# Driver.net
KiCad netlist of a schematic drawn in Altium Designer
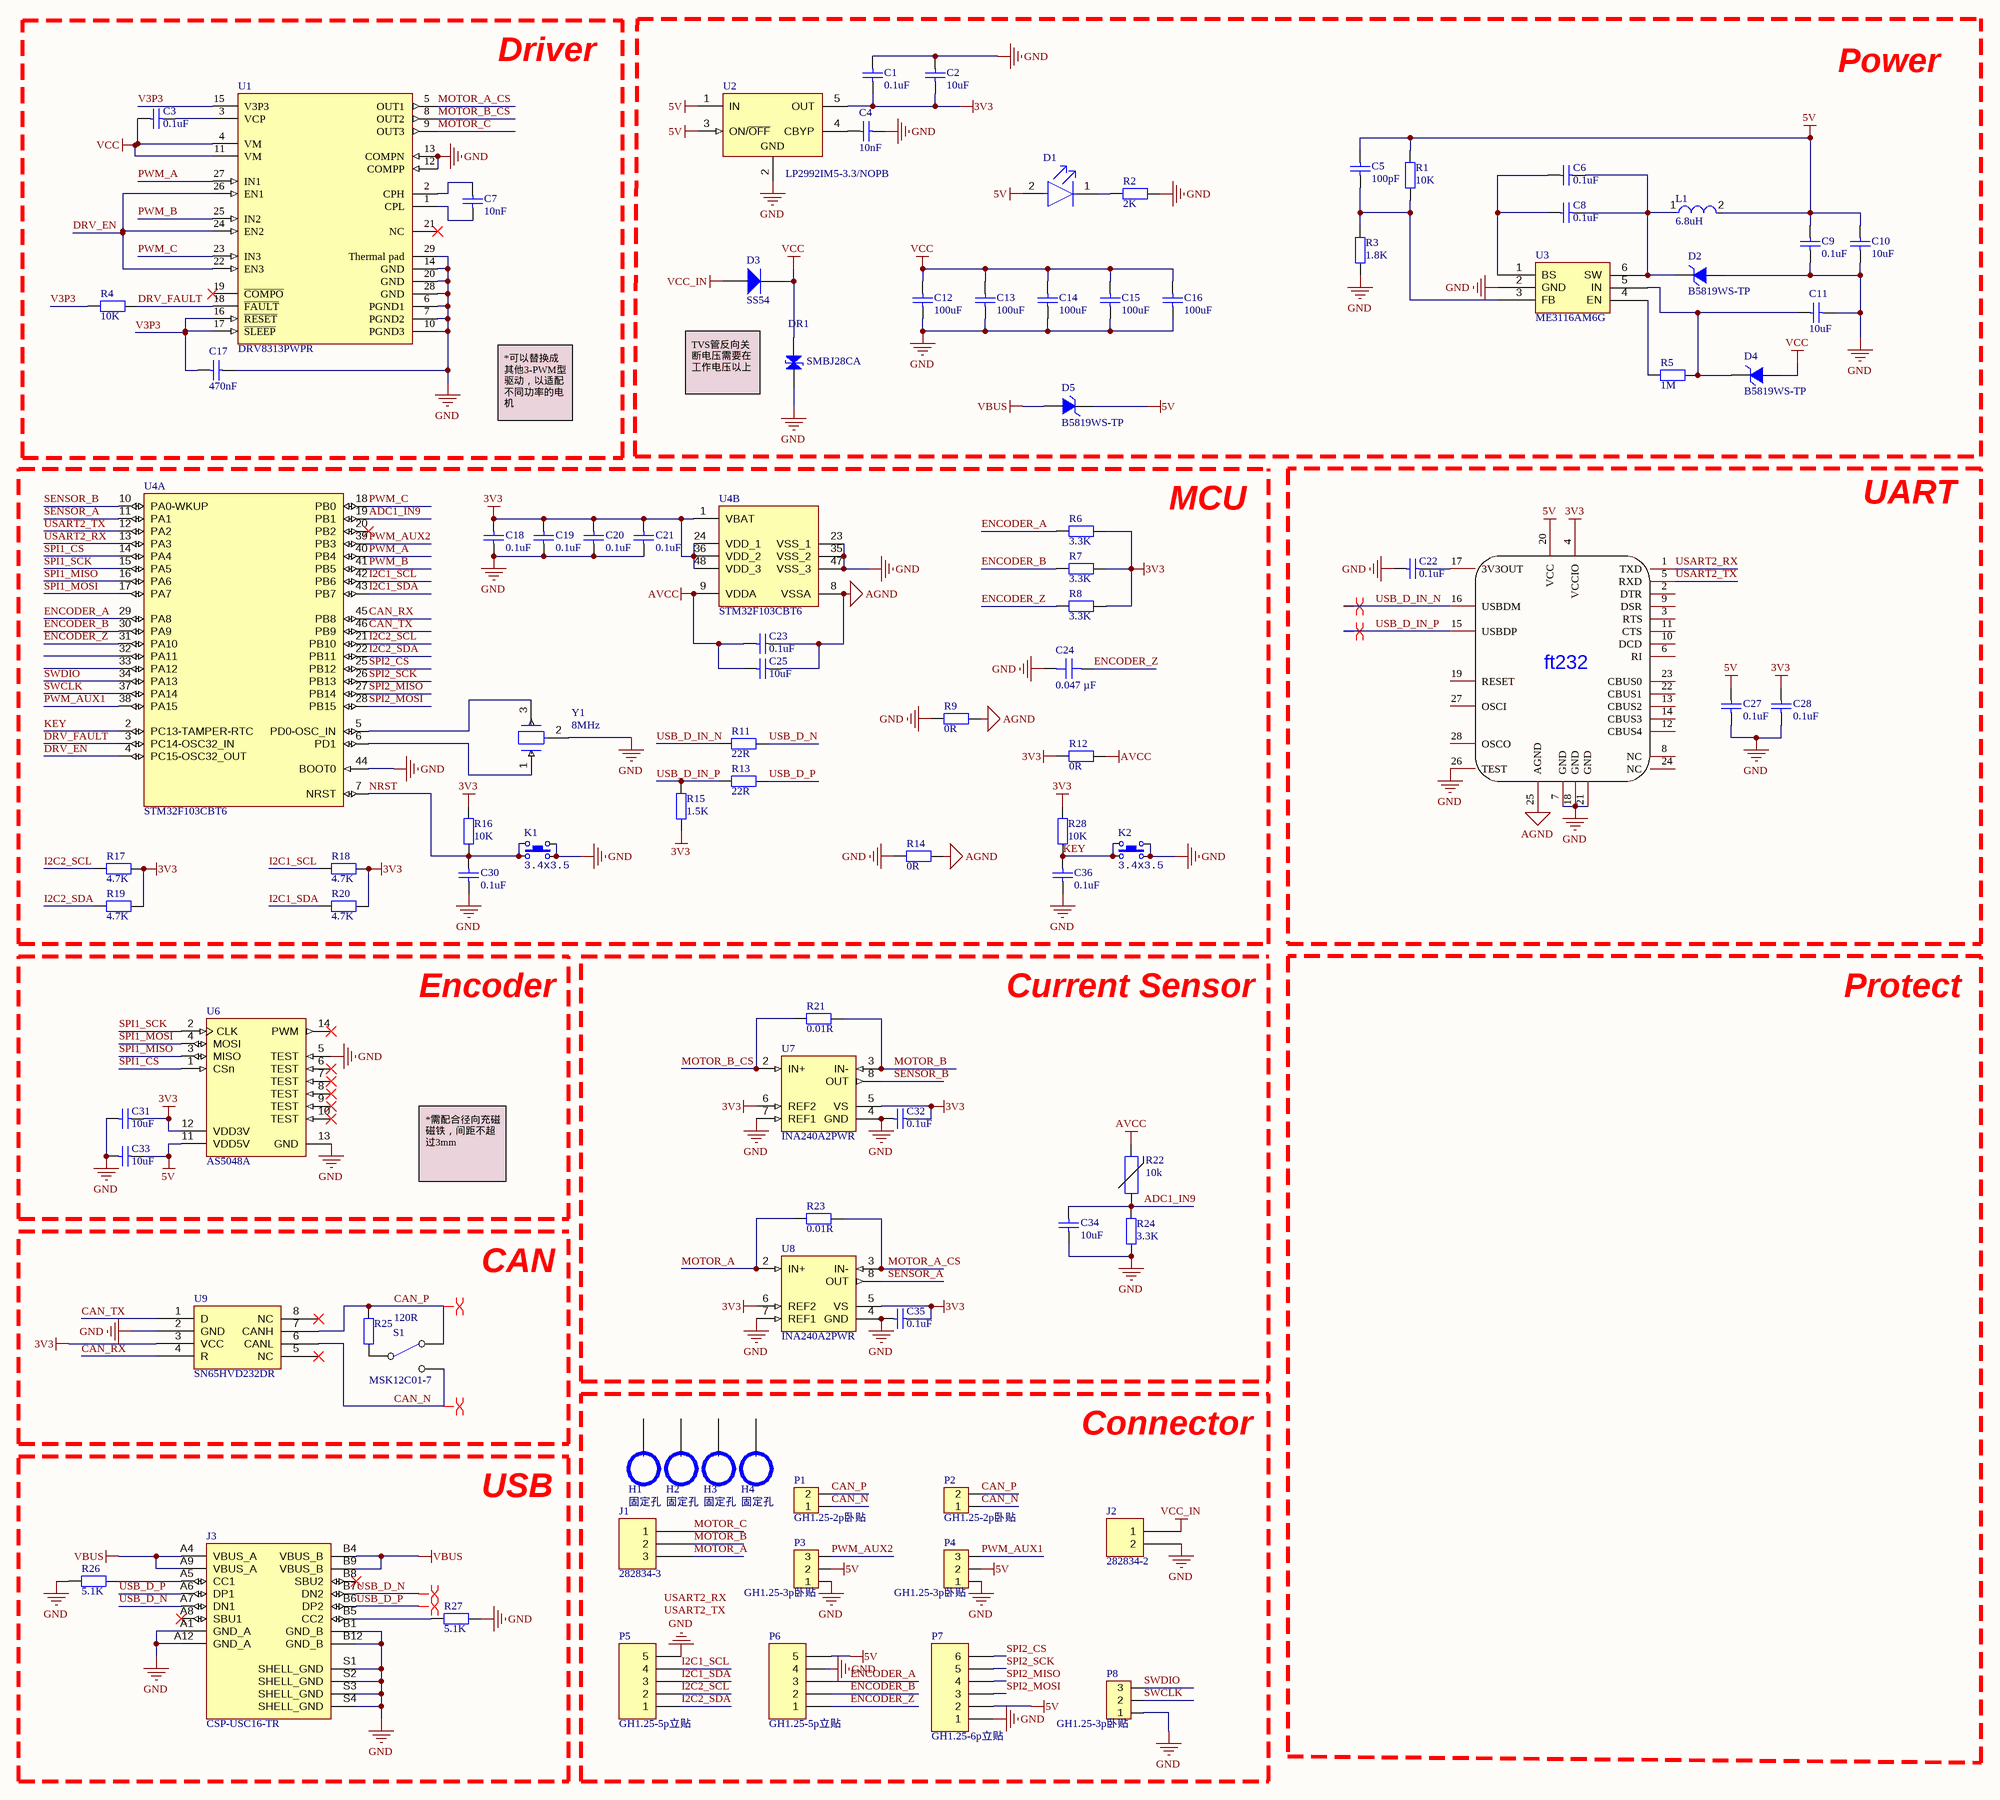
[diagram p0: Driver.SchDoc]

(export (version "E")
  (design (tool "Eeschema 10.0.6"))
  (components
    (comp (ref "C1")
      (value "0.1uF")
      (footprint "C 0402_L")
      (description "贴片电容")
      (libsource (lib "Miscellaneous Devices LC") (part "0402 100nF (104) 10% 16V"))
    )
    (comp (ref "C2")
      (value "10uF")
      (footprint "C 0402_L")
      (description "贴片电容")
      (libsource (lib "Miscellaneous Devices LC") (part "0402 100nF (104) 10% 16V"))
    )
    (comp (ref "C3")
      (value "0.1uF")
      (footprint "C 0402_L")
      (description "贴片电容")
      (libsource (lib "Miscellaneous Devices LC") (part "0402 100nF (104) 10% 16V"))
    )
    (comp (ref "C4")
      (value "10nF")
      (footprint "C 0402_L")
      (description "贴片电容")
      (libsource (lib "Miscellaneous Devices LC") (part "0402 100nF (104) 10% 16V"))
    )
    (comp (ref "C5")
      (value "100pF")
      (footprint "C 0402_L")
      (description "贴片电容")
      (libsource (lib "Miscellaneous Devices LC") (part "0402 100pF (101) 5% 50V"))
    )
    (comp (ref "C6")
      (value "0.1uF")
      (footprint "C 0402_L")
      (description "贴片电容")
      (libsource (lib "Miscellaneous Devices LC") (part "0402 100nF (104) 10% 16V"))
    )
    (comp (ref "C7")
      (value "10nF")
      (footprint "C 0402_L")
      (description "贴片电容")
      (libsource (lib "Miscellaneous Devices LC") (part "0402 10nF (103) 10% 50V"))
    )
    (comp (ref "C8")
      (value "0.1uF")
      (footprint "C 0402_L")
      (description "贴片电容")
      (libsource (lib "Miscellaneous Devices LC") (part "0402 100nF (104) 10% 16V"))
    )
    (comp (ref "C9")
      (value "0.1uF")
      (footprint "C 0402_L")
      (description "贴片电容")
      (libsource (lib "Miscellaneous Devices LC") (part "0402 100nF (104) 10% 16V"))
    )
    (comp (ref "C10")
      (value "10uF")
      (footprint "C 0402_L")
      (description "贴片电容")
      (libsource (lib "Miscellaneous Devices LC") (part "0402 100nF (104) 10% 16V"))
    )
    (comp (ref "C11")
      (value "10uF")
      (footprint "C 0402_L")
      (description "贴片电容")
      (libsource (lib "Miscellaneous Devices LC") (part "0402 100nF (104) 10% 16V"))
    )
    (comp (ref "C12")
      (value "100uF")
      (footprint "CAPC3216X190X55LL30T25")
      (description "Chip Capacitor, 100 uF, +/- 20%, 6.3 V, -55 to 85 degC, 1206 (3216 Metric), RoHS, Tape and Reel")
      (fields (field (name "TOLERANCE") "20%") (field (name "PARTNUMBER") "GRM31CR60J107ME39L"))
      (libsource (lib "Altium Content Vault") (part "CAP-NP-2"))
    )
    (comp (ref "C13")
      (value "100uF")
      (footprint "CAPC3216X190X55LL30T25")
      (description "Chip Capacitor, 100 uF, +/- 20%, 6.3 V, -55 to 85 degC, 1206 (3216 Metric), RoHS, Tape and Reel")
      (fields (field (name "TOLERANCE") "20%") (field (name "PARTNUMBER") "GRM31CR60J107ME39L"))
      (libsource (lib "Altium Content Vault") (part "CAP-NP-2"))
    )
    (comp (ref "C14")
      (value "100uF")
      (footprint "CAPC3216X190X55LL30T25")
      (description "Chip Capacitor, 100 uF, +/- 20%, 6.3 V, -55 to 85 degC, 1206 (3216 Metric), RoHS, Tape and Reel")
      (fields (field (name "TOLERANCE") "20%") (field (name "PARTNUMBER") "GRM31CR60J107ME39L"))
      (libsource (lib "Altium Content Vault") (part "CAP-NP-2"))
    )
    (comp (ref "C15")
      (value "100uF")
      (footprint "CAPC3216X190X55LL30T25")
      (description "Chip Capacitor, 100 uF, +/- 20%, 6.3 V, -55 to 85 degC, 1206 (3216 Metric), RoHS, Tape and Reel")
      (fields (field (name "TOLERANCE") "20%") (field (name "PARTNUMBER") "GRM31CR60J107ME39L"))
      (libsource (lib "Altium Content Vault") (part "CAP-NP-2"))
    )
    (comp (ref "C16")
      (value "100uF")
      (footprint "CAPC3216X190X55LL30T25")
      (description "Chip Capacitor, 100 uF, +/- 20%, 6.3 V, -55 to 85 degC, 1206 (3216 Metric), RoHS, Tape and Reel")
      (fields (field (name "TOLERANCE") "20%") (field (name "PARTNUMBER") "GRM31CR60J107ME39L"))
      (libsource (lib "Altium Content Vault") (part "CAP-NP-2"))
    )
    (comp (ref "C17")
      (value "470nF")
      (footprint "C 0402_L")
      (description "贴片电容")
      (libsource (lib "Miscellaneous Devices LC") (part "0402 470nF (474) 10% 10V"))
    )
    (comp (ref "C18")
      (value "0.1uF")
      (footprint "C 0402_L")
      (description "贴片电容")
      (libsource (lib "Miscellaneous Devices LC") (part "0402 100nF (104) 10% 16V"))
    )
    (comp (ref "C19")
      (value "0.1uF")
      (footprint "C 0402_L")
      (description "贴片电容")
      (libsource (lib "Miscellaneous Devices LC") (part "0402 100nF (104) 10% 16V"))
    )
    (comp (ref "C20")
      (value "0.1uF")
      (footprint "C 0402_L")
      (description "贴片电容")
      (libsource (lib "Miscellaneous Devices LC") (part "0402 100nF (104) 10% 16V"))
    )
    (comp (ref "C21")
      (value "0.1uF")
      (footprint "C 0402_L")
      (description "贴片电容")
      (libsource (lib "Miscellaneous Devices LC") (part "0402 100nF (104) 10% 16V"))
    )
    (comp (ref "C22")
      (value "0.1uF")
      (footprint "C 0402_L")
      (description "贴片电容")
      (libsource (lib "Miscellaneous Devices LC") (part "0402 100nF (104) 10% 16V"))
    )
    (comp (ref "C23")
      (value "0.1uF")
      (footprint "C 0402_L")
      (description "贴片电容")
      (libsource (lib "Miscellaneous Devices LC") (part "0402 100nF (104) 10% 16V"))
    )
    (comp (ref "C24")
      (value "0.047 µF")
      (footprint "CAP 0402_1005")
      (description "CAP CER 0402 47NF 25V X7R 10%")
      (fields (field (name "PART NUMBER") "C0402C473K3REC7867") (field (name "MANUFACTURER") "KEMET"))
      (libsource (lib "Celestial Altium Library - altium_library") (part "Capacitor"))
    )
    (comp (ref "C25")
      (value "10uF")
      (footprint "C 0402_L")
      (description "贴片电容")
      (libsource (lib "Miscellaneous Devices LC") (part "0402 100nF (104) 10% 16V"))
    )
    (comp (ref "C27")
      (value "0.1uF")
      (footprint "C 0402_L")
      (description "贴片电容")
      (libsource (lib "Miscellaneous Devices LC") (part "0402 100nF (104) 10% 16V"))
    )
    (comp (ref "C28")
      (value "0.1uF")
      (footprint "C 0402_L")
      (description "贴片电容")
      (libsource (lib "Miscellaneous Devices LC") (part "0402 100nF (104) 10% 16V"))
    )
    (comp (ref "C30")
      (value "0.1uF")
      (footprint "C 0402_L")
      (description "贴片电容")
      (libsource (lib "Miscellaneous Devices LC") (part "0402 100nF (104) 10% 16V"))
    )
    (comp (ref "C31")
      (value "10uF")
      (footprint "C 0402_L")
      (description "贴片电容")
      (libsource (lib "Miscellaneous Devices LC") (part "0402 100nF (104) 10% 16V"))
    )
    (comp (ref "C32")
      (value "0.1uF")
      (footprint "C 0402_L")
      (description "贴片电容")
      (libsource (lib "Miscellaneous Devices LC") (part "0402 100nF (104) 10% 16V"))
    )
    (comp (ref "C33")
      (value "10uF")
      (footprint "C 0402_L")
      (description "贴片电容")
      (libsource (lib "Miscellaneous Devices LC") (part "0402 100nF (104) 10% 16V"))
    )
    (comp (ref "C34")
      (value "10uF")
      (footprint "C 0402_L")
      (description "贴片电容")
      (libsource (lib "Miscellaneous Devices LC") (part "0402 100nF (104) 10% 16V"))
    )
    (comp (ref "C35")
      (value "0.1uF")
      (footprint "C 0402_L")
      (description "贴片电容")
      (libsource (lib "Miscellaneous Devices LC") (part "0402 100nF (104) 10% 16V"))
    )
    (comp (ref "C36")
      (value "0.1uF")
      (footprint "C 0402_L")
      (description "贴片电容")
      (libsource (lib "Miscellaneous Devices LC") (part "0402 100nF (104) 10% 16V"))
    )
    (comp (ref "D1")
      (value "~")
      (footprint "FP-APHHS1005CGCK-MFG")
      (description "LED GREEN CLEAR CHIP SMD")
      (libsource (lib "Altium Content Vault") (part "8706943c75ba83719d021d2fdc84c58"))
    )
    (comp (ref "D2")
      (value "B5819WS-TP")
      (footprint "SOD-523")
      (description "5.1V/1W稳压管")
      (fields (field (name "版权归属") "源创客"))
      (libsource (lib "*") (part "1N4733"))
    )
    (comp (ref "D3")
      (value "SS54")
      (footprint "SMA(DO-214AC)_S1")
      (description "二极管")
      (libsource (lib "Miscellaneous Devices LC") (part "SMA(DO-214AC) SS54"))
    )
    (comp (ref "D4")
      (value "B5819WS-TP")
      (footprint "SOD-523")
      (description "5.1V/1W稳压管")
      (fields (field (name "版权归属") "源创客"))
      (libsource (lib "*") (part "1N4733"))
    )
    (comp (ref "D5")
      (value "B5819WS-TP")
      (footprint "SOD-523")
      (description "5.1V/1W稳压管")
      (fields (field (name "版权归属") "源创客"))
      (libsource (lib "*") (part "1N4733"))
    )
    (comp (ref "DR1")
      (value "SMBJ28CA")
      (footprint "SMB")
      (description "瞬态电压抑制二极管")
      (fields (field (name "版权归属") "源创客"))
      (libsource (lib "*") (part "DR"))
    )
    (comp (ref "H1") (value "固定孔") (footprint "铜柱孔3") (libsource (lib "Rocos-FOC") (part "固定孔")))
    (comp (ref "H2") (value "固定孔") (footprint "铜柱孔3") (libsource (lib "Rocos-FOC") (part "固定孔")))
    (comp (ref "H3") (value "固定孔") (footprint "铜柱孔3") (libsource (lib "Rocos-FOC") (part "固定孔")))
    (comp (ref "H4") (value "固定孔") (footprint "铜柱孔3") (libsource (lib "Rocos-FOC") (part "固定孔")))
    (comp (ref "J1")
      (value "282834-3")
      (footprint "TE 282834-3")
      (description "TERM BLK 3P SIDE ENT 2.54MM PCB")
      (fields (field (name "MANUFACTURER") "TE Connectivity AMP Connectors") (field (name "VOLTAGE") "150V"))
      (libsource (lib "Rocos-FOC") (part "3 Pin"))
    )
    (comp (ref "J2")
      (value "282834-2")
      (footprint "TE 282834-2")
      (description "TERM BLK 2P SIDE ENT 2.54MM PCB")
      (fields (field (name "MANUFACTURER") "TE Connectivity AMP Connectors") (field (name "VOLTAGE") "150V"))
      (libsource (lib "Rocos-FOC") (part "2 Pin"))
    )
    (comp (ref "J3")
      (value "CSP-USC16-TR")
      (footprint "VALCON_CSP-USC16-TR")
      (description "CSP-USC16-TR Valcon USB Type C Surface Mount PCB Socket")
      (fields (field (name "MF") "Valcon"))
      (libsource (lib "Rocos-FOC") (part "CSP-USC16-TR"))
    )
    (comp (ref "K1")
      (value "3.4x3.5")
      (footprint "ButtonTACT_3.5*3.55_90")
      (description "Button")
      (fields (field (name "Comment") "TACT 4P"))
      (libsource (lib "Ctrl-FOC-Lite") (part "ButtonTACT"))
    )
    (comp (ref "K2")
      (value "3.4x3.5")
      (footprint "ButtonTACT_3.5*3.55_90")
      (description "Button")
      (fields (field (name "Comment") "TACT 4P"))
      (libsource (lib "Ctrl-FOC-Lite") (part "ButtonTACT"))
    )
    (comp (ref "L1")
      (value "6.8uH")
      (footprint "FP-LQH2MCN_52-MFG")
      (description "Wire Wound Ferrite Inductor for Power Lines 6.8μH ±20% 1.6Ω 285mA 0806")
      (fields (field (name "TOLERANCE") "20%"))
      (libsource (lib "Altium Content Vault") (part "725321dda6339637d4d059423bc1c3c"))
    )
    (comp (ref "P1")
      (value "GH1.25-2p卧贴")
      (footprint "GH1.25-2P")
      (libsource (lib "Rocos-FOC") (part "SH1.0-2P"))
    )
    (comp (ref "P2")
      (value "GH1.25-2p卧贴")
      (footprint "GH1.25-2P")
      (libsource (lib "Rocos-FOC") (part "SH1.0-2P"))
    )
    (comp (ref "P3")
      (value "GH1.25-3p卧贴")
      (footprint "GH1.25-3P")
      (description "Header")
      (libsource (lib "Rocos-FOC") (part "HDR1x3_2.54"))
    )
    (comp (ref "P4")
      (value "GH1.25-3p卧贴")
      (footprint "GH1.25-3P")
      (description "Header")
      (libsource (lib "Rocos-FOC") (part "HDR1x3_2.54"))
    )
    (comp (ref "P5")
      (value "GH1.25-5p立贴")
      (footprint "GH1.25-5p")
      (description "Header, 5-Pin")
      (fields (field (name "PUBLISHER") "Altium Limited"))
      (libsource (lib "Rocos-FOC") (part "MHDR1X5"))
    )
    (comp (ref "P6")
      (value "GH1.25-5p立贴")
      (footprint "GH1.25-5p")
      (description "Header, 5-Pin")
      (fields (field (name "PUBLISHER") "Altium Limited"))
      (libsource (lib "Rocos-FOC") (part "MHDR1X5"))
    )
    (comp (ref "P7")
      (value "GH1.25-6p立贴")
      (footprint "GH1.25-6p")
      (description "Header, 6-Pin")
      (fields (field (name "PUBLISHER") "Altium Limited"))
      (libsource (lib "Rocos-FOC") (part "MHDR1X6"))
    )
    (comp (ref "P8")
      (value "GH1.25-3p卧贴")
      (footprint "GH1.25-3P")
      (description "Header")
      (libsource (lib "Rocos-FOC") (part "HDR1x3_2.54"))
    )
    (comp (ref "R1")
      (value "10K")
      (footprint "R 0402_L")
      (description "贴片电阻")
      (libsource (lib "") (part "0402 1.2KΩ (1201) 1%_1"))
    )
    (comp (ref "R2")
      (value "2K")
      (footprint "R 0402_L")
      (description "贴片电阻")
      (libsource (lib "") (part "0402 2KΩ (2001) 1%_1"))
    )
    (comp (ref "R3")
      (value "1.8K")
      (footprint "R 0402_L")
      (description "贴片电阻")
      (libsource (lib "") (part "0402 1.2KΩ (1201) 1%_1"))
    )
    (comp (ref "R4")
      (value "10K")
      (footprint "R 0402_L")
      (description "贴片电阻")
      (libsource (lib "Miscellaneous Devices LC") (part "0402 1.2KΩ (1201) 1%"))
    )
    (comp (ref "R5")
      (value "1M")
      (footprint "R 0402_L")
      (description "贴片电阻")
      (libsource (lib "Miscellaneous Devices LC") (part "0402 2KΩ (2001) 1%"))
    )
    (comp (ref "R6")
      (value "3.3K")
      (footprint "R 0402_L")
      (description "贴片电阻")
      (libsource (lib "Miscellaneous Devices LC") (part "0402 3.3KΩ (3301) 1%"))
    )
    (comp (ref "R7")
      (value "3.3K")
      (footprint "R 0402_L")
      (description "贴片电阻")
      (libsource (lib "Miscellaneous Devices LC") (part "0402 3.3KΩ (3301) 1%"))
    )
    (comp (ref "R8")
      (value "3.3K")
      (footprint "R 0402_L")
      (description "贴片电阻")
      (libsource (lib "Miscellaneous Devices LC") (part "0402 3.3KΩ (3301) 1%"))
    )
    (comp (ref "R9")
      (value "0R")
      (footprint "R 0402_L")
      (description "贴片电阻")
      (libsource (lib "Miscellaneous Devices LC") (part "0402 0Ω (0R0) 1%"))
    )
    (comp (ref "R11")
      (value "22R")
      (footprint "R 0402_L")
      (description "贴片电阻")
      (libsource (lib "") (part "0402 22Ω (22R0) 1%_1"))
    )
    (comp (ref "R12")
      (value "0R")
      (footprint "R 0402_L")
      (description "贴片电阻")
      (libsource (lib "Miscellaneous Devices LC") (part "0402 0Ω (0R0) 1%"))
    )
    (comp (ref "R13")
      (value "22R")
      (footprint "R 0402_L")
      (description "贴片电阻")
      (libsource (lib "") (part "0402 22Ω (22R0) 1%_1"))
    )
    (comp (ref "R14")
      (value "0R")
      (footprint "R 0402_L")
      (description "贴片电阻")
      (libsource (lib "Miscellaneous Devices LC") (part "0402 0Ω (0R0) 1%"))
    )
    (comp (ref "R15")
      (value "1.5K")
      (footprint "R 0402_L")
      (description "贴片电阻")
      (libsource (lib "Miscellaneous Devices LC") (part "0402 1.5KΩ (1501) 1%"))
    )
    (comp (ref "R16")
      (value "10K")
      (footprint "R 0402_L")
      (description "贴片电阻")
      (libsource (lib "Miscellaneous Devices LC") (part "0402 10KΩ (1002) 1%"))
    )
    (comp (ref "R17")
      (value "4.7K")
      (footprint "R 0402_L")
      (description "贴片电阻")
      (libsource (lib "Miscellaneous Devices LC") (part "0402 4.7KΩ (4701) 1%"))
    )
    (comp (ref "R18")
      (value "4.7K")
      (footprint "R 0402_L")
      (description "贴片电阻")
      (libsource (lib "Miscellaneous Devices LC") (part "0402 4.7KΩ (4701) 1%"))
    )
    (comp (ref "R19")
      (value "4.7K")
      (footprint "R 0402_L")
      (description "贴片电阻")
      (libsource (lib "Miscellaneous Devices LC") (part "0402 4.7KΩ (4701) 1%"))
    )
    (comp (ref "R20")
      (value "4.7K")
      (footprint "R 0402_L")
      (description "贴片电阻")
      (libsource (lib "Miscellaneous Devices LC") (part "0402 4.7KΩ (4701) 1%"))
    )
    (comp (ref "R21")
      (value "0.01R")
      (footprint "R 0402_L")
      (description "贴片电阻")
      (libsource (lib "Miscellaneous Devices LC") (part "0402 22Ω (22R0) 1%"))
    )
    (comp (ref "R22")
      (value "10k")
      (footprint "RES_0402")
      (description "THERMISTOR 10K OHM NTC 0402 SMD")
      (fields (field (name "Comment") "NCP15XH103F03RC"))
      (libsource (lib "Ctrl-FOC-Lite") (part "NCP15XH103F03RC"))
    )
    (comp (ref "R23")
      (value "0.01R")
      (footprint "R 0402_L")
      (description "贴片电阻")
      (libsource (lib "Miscellaneous Devices LC") (part "0402 22Ω (22R0) 1%"))
    )
    (comp (ref "R24")
      (value "3.3K")
      (footprint "R 0402_L")
      (description "贴片电阻")
      (libsource (lib "") (part "0402 3.3KΩ (3301) 1%_1"))
    )
    (comp (ref "R25")
      (value "120R")
      (footprint "R 0402_L")
      (description "贴片电阻")
      (libsource (lib "Miscellaneous Devices LC") (part "0402 120Ω (1200) 1%"))
    )
    (comp (ref "R26")
      (value "5.1K")
      (footprint "R 0402_L")
      (description "贴片电阻")
      (libsource (lib "Miscellaneous Devices LC") (part "0402 1.2KΩ (1201) 1%"))
    )
    (comp (ref "R27")
      (value "5.1K")
      (footprint "R 0402_L")
      (description "贴片电阻")
      (libsource (lib "Miscellaneous Devices LC") (part "0402 1.2KΩ (1201) 1%"))
    )
    (comp (ref "R28")
      (value "10K")
      (footprint "R 0402_L")
      (description "贴片电阻")
      (libsource (lib "Miscellaneous Devices LC") (part "0402 10KΩ (1002) 1%"))
    )
    (comp (ref "S1")
      (value "MSK12C01-7")
      (footprint "MSK-12C01-07")
      (libsource (lib "闹钟") (part "T8013三脚两档钮子开关"))
    )
    (comp (ref "U1")
      (value "DRV8313PWPR")
      (footprint "FP-PWP0028C-IPC_B")
      (description "IC MOTOR DRIVER 8V-60V 28HTSSOP")
      (libsource (lib "Altium Content Vault") (part "6c5e8d1d79df7918d4eb9ae5de6b4b8"))
    )
    (comp (ref "U2")
      (value "LP2992IM5-3.3/NOPB")
      (footprint "DBV0005A_L")
      (description "Micropower 250 mA Low-Noise Ultra Low-Dropout Regulator, 5-pin SOT-23, Pb-Free")
      (fields (field (name "MANUFACTURER") "Texas Instruments"))
      (libsource (lib "Altium Content Vault") (part "PM-REG-LP2985-SOT5"))
    )
    (comp (ref "U3")
      (value "ME3116AM6G")
      (footprint "SOT-23-6")
      (description "DC/DC降压型稳压器")
      (libsource (lib "Rocos-FOC") (part "ME3116AM6G"))
    )
    (comp (ref "U4")
      (value "STM32F103CBT6")
      (footprint "LQFP-48_7x7x05P")
      (description "ARM")
      (libsource (lib "Rocos-FOC") (part "STM32F103CBT6"))
    )
    (comp (ref "U5")
      (value "FT232RL-REEL")
      (footprint "SSOP28")
      (fields (field (name "MANUFACTURER") "FTDI(飞特帝亚)"))
      (libsource (lib "altium-import") (part "root_0_FT232RL-REEL_"))
    )
    (comp (ref "U6")
      (value "AS5048A")
      (footprint "TSSOP-14")
      (description "14 位旋转式位置传感器")
      (libsource (lib "Rocos-FOC") (part "AS5048A"))
    )
    (comp (ref "U7")
      (value "INA240A2PWR")
      (footprint "SOP65 P640X120-8N")
      (fields (field (name "MF") "Texas Instruments"))
      (libsource (lib "Rocos-FOC") (part "INA240A2PWR"))
    )
    (comp (ref "U8")
      (value "INA240A2PWR")
      (footprint "SOP65 P640X120-8N")
      (fields (field (name "MF") "Texas Instruments"))
      (libsource (lib "Rocos-FOC") (part "INA240A2PWR"))
    )
    (comp (ref "U9")
      (value "SN65HVD232D")
      (footprint "SO-8")
      (fields
        (field (name "MANUFACTURER") "Texas Instruments")
        (field (name "MANUFACTURER PART NUMBER") "SN65HVD232DR")
      )
      (libsource (lib "Rocos-FOC") (part "SN65HVD232D"))
    )
    (comp (ref "Y1")
      (value "8MHz")
      (footprint "FP-CSTNE8M00GH5C000R0-MFG")
      (description "CERAMIC RES 8.0000MHZ 33PF SMD")
      (libsource (lib "Altium Content Vault") (part "7d37667f5012bb31280c8009ddd0b1c"))
    )
  )
  (nets
    (net (code "1") (name "/ADC1_IN9") (class "Default")
      (node (ref "C34") (pin "1") (pinfunction "1_1") (pintype "passive"))
      (node (ref "R22") (pin "1") (pinfunction "0_1") (pintype "passive"))
      (node (ref "R24") (pin "2") (pinfunction "2_2") (pintype "passive"))
      (node (ref "U4") (pin "19") (pinfunction "PB1_19") (pintype "bidirectional"))
    )
    (net (code "2") (name "/CAN_N") (class "Default")
      (node (ref "P1") (pin "1") (pinfunction "1_1") (pintype "passive"))
      (node (ref "P2") (pin "1") (pinfunction "1_1") (pintype "passive"))
      (node (ref "S1") (pin "3") (pinfunction "3_3") (pintype "passive"))
      (node (ref "U9") (pin "6") (pinfunction "CANL_6") (pintype "passive"))
    )
    (net (code "3") (name "/CAN_P") (class "Default")
      (node (ref "P1") (pin "2") (pinfunction "2_2") (pintype "passive"))
      (node (ref "P2") (pin "2") (pinfunction "2_2") (pintype "passive"))
      (node (ref "R25") (pin "2") (pinfunction "2_2") (pintype "passive"))
      (node (ref "S1") (pin "1") (pinfunction "1_1") (pintype "passive"))
      (node (ref "U9") (pin "7") (pinfunction "CANH_7") (pintype "passive"))
    )
    (net (code "4") (name "/CAN_RX") (class "Default")
      (node (ref "U4") (pin "45") (pinfunction "PB8_45") (pintype "bidirectional"))
      (node (ref "U9") (pin "4") (pinfunction "R_4") (pintype "passive"))
    )
    (net (code "5") (name "/CAN_TX") (class "Default")
      (node (ref "U4") (pin "46") (pinfunction "PB9_46") (pintype "bidirectional"))
      (node (ref "U9") (pin "1") (pinfunction "D_1") (pintype "passive"))
    )
    (net (code "6") (name "/DRV_EN") (class "Default")
      (node (ref "U1") (pin "22") (pinfunction "EN3_22") (pintype "input"))
      (node (ref "U1") (pin "24") (pinfunction "EN2_24") (pintype "input"))
      (node (ref "U1") (pin "26") (pinfunction "EN1_26") (pintype "input"))
      (node (ref "U4") (pin "4") (pinfunction "PC15-OSC32_OUT_4") (pintype "bidirectional"))
    )
    (net (code "7") (name "/DRV_FAULT") (class "Default")
      (node (ref "R4") (pin "1") (pinfunction "1_1") (pintype "passive"))
      (node (ref "U1") (pin "18") (pinfunction "~{FAULT}_18") (pintype "open_collector"))
      (node (ref "U4") (pin "3") (pinfunction "PC14-OSC32_IN_3") (pintype "bidirectional"))
    )
    (net (code "8") (name "/ENCODER_A") (class "Default")
      (node (ref "P6") (pin "3") (pinfunction "3_3") (pintype "passive"))
      (node (ref "R6") (pin "1") (pinfunction "1_1") (pintype "passive"))
      (node (ref "U4") (pin "29") (pinfunction "PA8_29") (pintype "bidirectional"))
    )
    (net (code "9") (name "/ENCODER_B") (class "Default")
      (node (ref "P6") (pin "2") (pinfunction "2_2") (pintype "passive"))
      (node (ref "R7") (pin "1") (pinfunction "1_1") (pintype "passive"))
      (node (ref "U4") (pin "30") (pinfunction "PA9_30") (pintype "bidirectional"))
    )
    (net (code "10") (name "/ENCODER_Z") (class "Default")
      (node (ref "C24") (pin "2") (pinfunction "2_2") (pintype "passive"))
      (node (ref "P6") (pin "1") (pinfunction "1_1") (pintype "passive"))
      (node (ref "R8") (pin "1") (pinfunction "1_1") (pintype "passive"))
      (node (ref "U4") (pin "31") (pinfunction "PA10_31") (pintype "bidirectional"))
    )
    (net (code "11") (name "/I2C1_SCL") (class "Default")
      (node (ref "P5") (pin "4") (pinfunction "4_4") (pintype "passive"))
      (node (ref "R18") (pin "1") (pinfunction "1_1") (pintype "passive"))
      (node (ref "U4") (pin "42") (pinfunction "PB6_42") (pintype "bidirectional"))
    )
    (net (code "12") (name "/I2C1_SDA") (class "Default")
      (node (ref "P5") (pin "3") (pinfunction "3_3") (pintype "passive"))
      (node (ref "R20") (pin "1") (pinfunction "1_1") (pintype "passive"))
      (node (ref "U4") (pin "43") (pinfunction "PB7_43") (pintype "bidirectional"))
    )
    (net (code "13") (name "/I2C2_SCL") (class "Default")
      (node (ref "P5") (pin "2") (pinfunction "2_2") (pintype "passive"))
      (node (ref "R17") (pin "1") (pinfunction "1_1") (pintype "passive"))
      (node (ref "U4") (pin "21") (pinfunction "PB10_21") (pintype "bidirectional"))
    )
    (net (code "14") (name "/I2C2_SDA") (class "Default")
      (node (ref "P5") (pin "1") (pinfunction "1_1") (pintype "passive"))
      (node (ref "R19") (pin "1") (pinfunction "1_1") (pintype "passive"))
      (node (ref "U4") (pin "22") (pinfunction "PB11_22") (pintype "bidirectional"))
    )
    (net (code "15") (name "/KEY") (class "Default")
      (node (ref "C36") (pin "1") (pinfunction "1_1") (pintype "passive"))
      (node (ref "K2") (pin "1") (pinfunction "1_1") (pintype "passive"))
      (node (ref "K2") (pin "3") (pinfunction "3_3") (pintype "passive"))
      (node (ref "R28") (pin "1") (pinfunction "1_1") (pintype "passive"))
      (node (ref "U4") (pin "2") (pinfunction "PC13-TAMPER-RTC_2") (pintype "bidirectional"))
    )
    (net (code "16") (name "/MOTOR_A") (class "Default")
      (node (ref "J1") (pin "3") (pinfunction "3_3") (pintype "passive"))
      (node (ref "R23") (pin "2") (pinfunction "2_2") (pintype "passive"))
      (node (ref "U8") (pin "2") (pinfunction "IN+_2") (pintype "input"))
    )
    (net (code "17") (name "/MOTOR_A_CS") (class "Default")
      (node (ref "R23") (pin "1") (pinfunction "1_1") (pintype "passive"))
      (node (ref "U1") (pin "5") (pinfunction "OUT1_5") (pintype "output"))
      (node (ref "U8") (pin "3") (pinfunction "IN-_3") (pintype "input"))
    )
    (net (code "18") (name "/MOTOR_B") (class "Default")
      (node (ref "J1") (pin "2") (pinfunction "2_2") (pintype "passive"))
      (node (ref "R21") (pin "1") (pinfunction "1_1") (pintype "passive"))
      (node (ref "U7") (pin "3") (pinfunction "IN-_3") (pintype "input"))
    )
    (net (code "19") (name "/MOTOR_B_CS") (class "Default")
      (node (ref "R21") (pin "2") (pinfunction "2_2") (pintype "passive"))
      (node (ref "U1") (pin "8") (pinfunction "OUT2_8") (pintype "output"))
      (node (ref "U7") (pin "2") (pinfunction "IN+_2") (pintype "input"))
    )
    (net (code "20") (name "/MOTOR_C") (class "Default")
      (node (ref "J1") (pin "1") (pinfunction "1_1") (pintype "passive"))
      (node (ref "U1") (pin "9") (pinfunction "OUT3_9") (pintype "output"))
    )
    (net (code "21") (name "/NRST") (class "Default")
      (node (ref "C30") (pin "1") (pinfunction "1_1") (pintype "passive"))
      (node (ref "K1") (pin "1") (pinfunction "1_1") (pintype "passive"))
      (node (ref "K1") (pin "3") (pinfunction "3_3") (pintype "passive"))
      (node (ref "R16") (pin "1") (pinfunction "1_1") (pintype "passive"))
      (node (ref "U4") (pin "7") (pinfunction "NRST_7") (pintype "bidirectional"))
    )
    (net (code "22") (name "/PWM_A") (class "Default")
      (node (ref "U1") (pin "27") (pinfunction "IN1_27") (pintype "input"))
      (node (ref "U4") (pin "40") (pinfunction "PB4_40") (pintype "bidirectional"))
    )
    (net (code "23") (name "/PWM_AUX1") (class "Default")
      (node (ref "P4") (pin "3") (pinfunction "3_3") (pintype "passive"))
      (node (ref "U4") (pin "38") (pinfunction "PA15_38") (pintype "bidirectional"))
    )
    (net (code "24") (name "/PWM_AUX2") (class "Default")
      (node (ref "P3") (pin "3") (pinfunction "3_3") (pintype "passive"))
      (node (ref "U4") (pin "39") (pinfunction "PB3_39") (pintype "bidirectional"))
    )
    (net (code "25") (name "/PWM_B") (class "Default")
      (node (ref "U1") (pin "25") (pinfunction "IN2_25") (pintype "input"))
      (node (ref "U4") (pin "41") (pinfunction "PB5_41") (pintype "bidirectional"))
    )
    (net (code "26") (name "/PWM_C") (class "Default")
      (node (ref "U1") (pin "23") (pinfunction "IN3_23") (pintype "input"))
      (node (ref "U4") (pin "18") (pinfunction "PB0_18") (pintype "bidirectional"))
    )
    (net (code "27") (name "/SENSOR_A") (class "Default")
      (node (ref "U4") (pin "11") (pinfunction "PA1_11") (pintype "bidirectional"))
      (node (ref "U8") (pin "8") (pinfunction "OUT_8") (pintype "output"))
    )
    (net (code "28") (name "/SENSOR_B") (class "Default")
      (node (ref "U4") (pin "10") (pinfunction "PA0-WKUP_10") (pintype "bidirectional"))
      (node (ref "U7") (pin "8") (pinfunction "OUT_8") (pintype "output"))
    )
    (net (code "29") (name "/SPI1_CS") (class "Default")
      (node (ref "U4") (pin "14") (pinfunction "PA4_14") (pintype "bidirectional"))
      (node (ref "U6") (pin "1") (pinfunction "CSn_1") (pintype "input"))
    )
    (net (code "30") (name "/SPI1_MISO") (class "Default")
      (node (ref "U4") (pin "16") (pinfunction "PA6_16") (pintype "bidirectional"))
      (node (ref "U6") (pin "3") (pinfunction "MISO_3") (pintype "bidirectional"))
    )
    (net (code "31") (name "/SPI1_MOSI") (class "Default")
      (node (ref "U4") (pin "17") (pinfunction "PA7_17") (pintype "bidirectional"))
      (node (ref "U6") (pin "4") (pinfunction "MOSI_4") (pintype "bidirectional"))
    )
    (net (code "32") (name "/SPI1_SCK") (class "Default")
      (node (ref "U4") (pin "15") (pinfunction "PA5_15") (pintype "bidirectional"))
      (node (ref "U6") (pin "2") (pinfunction "CLK_2") (pintype "input"))
    )
    (net (code "33") (name "/SPI2_CS") (class "Default")
      (node (ref "P7") (pin "6") (pinfunction "6_6") (pintype "passive"))
      (node (ref "U4") (pin "25") (pinfunction "PB12_25") (pintype "bidirectional"))
    )
    (net (code "34") (name "/SPI2_MISO") (class "Default")
      (node (ref "P7") (pin "4") (pinfunction "4_4") (pintype "passive"))
      (node (ref "U4") (pin "27") (pinfunction "PB14_27") (pintype "bidirectional"))
    )
    (net (code "35") (name "/SPI2_MOSI") (class "Default")
      (node (ref "P7") (pin "3") (pinfunction "3_3") (pintype "passive"))
      (node (ref "U4") (pin "28") (pinfunction "PB15_28") (pintype "bidirectional"))
    )
    (net (code "36") (name "/SPI2_SCK") (class "Default")
      (node (ref "P7") (pin "5") (pinfunction "5_5") (pintype "passive"))
      (node (ref "U4") (pin "26") (pinfunction "PB13_26") (pintype "bidirectional"))
    )
    (net (code "37") (name "/SWCLK") (class "Default")
      (node (ref "P8") (pin "2") (pinfunction "2_2") (pintype "passive"))
      (node (ref "U4") (pin "37") (pinfunction "PA14_37") (pintype "bidirectional"))
    )
    (net (code "38") (name "/SWDIO") (class "Default")
      (node (ref "P8") (pin "3") (pinfunction "3_3") (pintype "passive"))
      (node (ref "U4") (pin "34") (pinfunction "PA13_34") (pintype "bidirectional"))
    )
    (net (code "39") (name "/USART2_RX") (class "Default")
      (node (ref "U4") (pin "13") (pinfunction "PA3_13") (pintype "bidirectional"))
      (node (ref "U5") (pin "1") (pinfunction "TXD_1") (pintype "passive"))
    )
    (net (code "40") (name "/USART2_TX") (class "Default")
      (node (ref "U4") (pin "12") (pinfunction "PA2_12") (pintype "bidirectional"))
      (node (ref "U5") (pin "5") (pinfunction "RXD_5") (pintype "passive"))
    )
    (net (code "41") (name "/USB_D_IN_N") (class "Default")
      (node (ref "R11") (pin "1") (pinfunction "1_1") (pintype "passive"))
      (node (ref "U5") (pin "16") (pinfunction "USBDM_16") (pintype "passive"))
    )
    (net (code "42") (name "/USB_D_IN_P") (class "Default")
      (node (ref "R13") (pin "1") (pinfunction "1_1") (pintype "passive"))
      (node (ref "R15") (pin "2") (pinfunction "2_2") (pintype "passive"))
      (node (ref "U5") (pin "15") (pinfunction "USBDP_15") (pintype "passive"))
    )
    (net (code "43") (name "/USB_D_N") (class "Default")
      (node (ref "J3") (pin "A7") (pinfunction "DN1_A7") (pintype "bidirectional"))
      (node (ref "J3") (pin "B7") (pinfunction "DN2_B7") (pintype "bidirectional"))
      (node (ref "R11") (pin "2") (pinfunction "2_2") (pintype "passive"))
    )
    (net (code "44") (name "/USB_D_P") (class "Default")
      (node (ref "J3") (pin "A6") (pinfunction "DP1_A6") (pintype "bidirectional"))
      (node (ref "J3") (pin "B6") (pinfunction "DP2_B6") (pintype "bidirectional"))
      (node (ref "R13") (pin "2") (pinfunction "2_2") (pintype "passive"))
    )
    (net (code "45") (name "/V3P3") (class "Default")
      (node (ref "C17") (pin "1") (pinfunction "1_1") (pintype "passive"))
      (node (ref "R4") (pin "2") (pinfunction "2_2") (pintype "passive"))
      (node (ref "U1") (pin "15") (pinfunction "V3P3_15") (pintype "power_in"))
      (node (ref "U1") (pin "16") (pinfunction "~{RESET}_16") (pintype "input"))
      (node (ref "U1") (pin "17") (pinfunction "~{SLEEP}_17") (pintype "input"))
    )
    (net (code "46") (name "3V3") (class "Default")
      (node (ref "C1") (pin "1") (pinfunction "1_1") (pintype "passive"))
      (node (ref "C18") (pin "1") (pinfunction "1_1") (pintype "passive"))
      (node (ref "C19") (pin "1") (pinfunction "1_1") (pintype "passive"))
      (node (ref "C2") (pin "1") (pinfunction "1_1") (pintype "passive"))
      (node (ref "C20") (pin "1") (pinfunction "1_1") (pintype "passive"))
      (node (ref "C21") (pin "1") (pinfunction "1_1") (pintype "passive"))
      (node (ref "C28") (pin "1") (pinfunction "1_1") (pintype "passive"))
      (node (ref "C31") (pin "1") (pinfunction "1_1") (pintype "passive"))
      (node (ref "C32") (pin "1") (pinfunction "1_1") (pintype "passive"))
      (node (ref "C35") (pin "1") (pinfunction "1_1") (pintype "passive"))
      (node (ref "R12") (pin "1") (pinfunction "1_1") (pintype "passive"))
      (node (ref "R15") (pin "1") (pinfunction "1_1") (pintype "passive"))
      (node (ref "R16") (pin "2") (pinfunction "2_2") (pintype "passive"))
      (node (ref "R17") (pin "2") (pinfunction "2_2") (pintype "passive"))
      (node (ref "R18") (pin "2") (pinfunction "2_2") (pintype "passive"))
      (node (ref "R19") (pin "2") (pinfunction "2_2") (pintype "passive"))
      (node (ref "R20") (pin "2") (pinfunction "2_2") (pintype "passive"))
      (node (ref "R28") (pin "2") (pinfunction "2_2") (pintype "passive"))
      (node (ref "R6") (pin "2") (pinfunction "2_2") (pintype "passive"))
      (node (ref "R7") (pin "2") (pinfunction "2_2") (pintype "passive"))
      (node (ref "R8") (pin "2") (pinfunction "2_2") (pintype "passive"))
      (node (ref "U2") (pin "5") (pinfunction "OUT_5") (pintype "power_in"))
      (node (ref "U4") (pin "1") (pinfunction "VBAT_1") (pintype "power_in"))
      (node (ref "U4") (pin "24") (pinfunction "VDD_1_24") (pintype "power_in"))
      (node (ref "U4") (pin "36") (pinfunction "VDD_2_36") (pintype "power_in"))
      (node (ref "U4") (pin "48") (pinfunction "VDD_3_48") (pintype "power_in"))
      (node (ref "U5") (pin "4") (pinfunction "VCCIO_4") (pintype "passive"))
      (node (ref "U6") (pin "12") (pinfunction "VDD3V_12") (pintype "power_in"))
      (node (ref "U7") (pin "5") (pinfunction "VS_5") (pintype "power_in"))
      (node (ref "U7") (pin "6") (pinfunction "REF2_6") (pintype "input"))
      (node (ref "U8") (pin "5") (pinfunction "VS_5") (pintype "power_in"))
      (node (ref "U8") (pin "6") (pinfunction "REF2_6") (pintype "input"))
      (node (ref "U9") (pin "3") (pinfunction "VCC_3") (pintype "passive"))
    )
    (net (code "47") (name "5V") (class "Default")
      (node (ref "C10") (pin "2") (pinfunction "2_2") (pintype "passive"))
      (node (ref "C27") (pin "1") (pinfunction "1_1") (pintype "passive"))
      (node (ref "C33") (pin "1") (pinfunction "1_1") (pintype "passive"))
      (node (ref "C5") (pin "2") (pinfunction "2_2") (pintype "passive"))
      (node (ref "C9") (pin "1") (pinfunction "1_1") (pintype "passive"))
      (node (ref "D1") (pin "2") (pinfunction "A_2") (pintype "passive"))
      (node (ref "D5") (pin "2") (pinfunction "K_2") (pintype "passive"))
      (node (ref "L1") (pin "2") (pinfunction "2_2") (pintype "passive"))
      (node (ref "P3") (pin "2") (pinfunction "2_2") (pintype "passive"))
      (node (ref "P4") (pin "2") (pinfunction "2_2") (pintype "passive"))
      (node (ref "P6") (pin "5") (pinfunction "5_5") (pintype "passive"))
      (node (ref "P7") (pin "2") (pinfunction "2_2") (pintype "passive"))
      (node (ref "R1") (pin "2") (pinfunction "2_2") (pintype "passive"))
      (node (ref "U2") (pin "1") (pinfunction "IN_1") (pintype "power_in"))
      (node (ref "U2") (pin "3") (pinfunction "ON/~{OFF}_3") (pintype "input"))
      (node (ref "U5") (pin "20") (pinfunction "VCC_20") (pintype "passive"))
      (node (ref "U6") (pin "11") (pinfunction "VDD5V_11") (pintype "power_in"))
    )
    (net (code "48") (name "AGND") (class "Default")
      (node (ref "C23") (pin "1") (pinfunction "1_1") (pintype "passive"))
      (node (ref "C25") (pin "1") (pinfunction "1_1") (pintype "passive"))
      (node (ref "R14") (pin "2") (pinfunction "2_2") (pintype "passive"))
      (node (ref "R9") (pin "2") (pinfunction "2_2") (pintype "passive"))
      (node (ref "U4") (pin "8") (pinfunction "VSSA_8") (pintype "power_in"))
      (node (ref "U5") (pin "25") (pinfunction "AGND_25") (pintype "passive"))
    )
    (net (code "49") (name "AVCC") (class "Default")
      (node (ref "C23") (pin "2") (pinfunction "2_2") (pintype "passive"))
      (node (ref "C25") (pin "2") (pinfunction "2_2") (pintype "passive"))
      (node (ref "R12") (pin "2") (pinfunction "2_2") (pintype "passive"))
      (node (ref "R22") (pin "2") (pinfunction "0_2") (pintype "passive"))
      (node (ref "U4") (pin "9") (pinfunction "VDDA_9") (pintype "power_in"))
    )
    (net (code "50") (name "GND") (class "Default")
      (node (ref "C1") (pin "2") (pinfunction "2_2") (pintype "passive"))
      (node (ref "C10") (pin "1") (pinfunction "1_1") (pintype "passive"))
      (node (ref "C11") (pin "1") (pinfunction "1_1") (pintype "passive"))
      (node (ref "C12") (pin "1") (pinfunction "1_1") (pintype "passive"))
      (node (ref "C13") (pin "1") (pinfunction "1_1") (pintype "passive"))
      (node (ref "C14") (pin "1") (pinfunction "1_1") (pintype "passive"))
      (node (ref "C15") (pin "1") (pinfunction "1_1") (pintype "passive"))
      (node (ref "C16") (pin "1") (pinfunction "1_1") (pintype "passive"))
      (node (ref "C17") (pin "2") (pinfunction "2_2") (pintype "passive"))
      (node (ref "C18") (pin "2") (pinfunction "2_2") (pintype "passive"))
      (node (ref "C19") (pin "2") (pinfunction "2_2") (pintype "passive"))
      (node (ref "C2") (pin "2") (pinfunction "2_2") (pintype "passive"))
      (node (ref "C20") (pin "2") (pinfunction "2_2") (pintype "passive"))
      (node (ref "C21") (pin "2") (pinfunction "2_2") (pintype "passive"))
      (node (ref "C22") (pin "2") (pinfunction "2_2") (pintype "passive"))
      (node (ref "C24") (pin "1") (pinfunction "1_1") (pintype "passive"))
      (node (ref "C27") (pin "2") (pinfunction "2_2") (pintype "passive"))
      (node (ref "C28") (pin "2") (pinfunction "2_2") (pintype "passive"))
      (node (ref "C30") (pin "2") (pinfunction "2_2") (pintype "passive"))
      (node (ref "C31") (pin "2") (pinfunction "2_2") (pintype "passive"))
      (node (ref "C32") (pin "2") (pinfunction "2_2") (pintype "passive"))
      (node (ref "C33") (pin "2") (pinfunction "2_2") (pintype "passive"))
      (node (ref "C34") (pin "2") (pinfunction "2_2") (pintype "passive"))
      (node (ref "C35") (pin "2") (pinfunction "2_2") (pintype "passive"))
      (node (ref "C36") (pin "2") (pinfunction "2_2") (pintype "passive"))
      (node (ref "C4") (pin "1") (pinfunction "1_1") (pintype "passive"))
      (node (ref "C9") (pin "2") (pinfunction "2_2") (pintype "passive"))
      (node (ref "D2") (pin "1") (pinfunction "A_1") (pintype "passive"))
      (node (ref "DR1") (pin "2") (pinfunction "K_2") (pintype "passive"))
      (node (ref "J2") (pin "2") (pinfunction "2_2") (pintype "passive"))
      (node (ref "J3") (pin "A1") (pinfunction "GND_A_A1") (pintype "power_in"))
      (node (ref "J3") (pin "A12") (pinfunction "GND_A_A12") (pintype "power_in"))
      (node (ref "J3") (pin "B1") (pinfunction "GND_B_B1") (pintype "power_in"))
      (node (ref "J3") (pin "B12") (pinfunction "GND_B_B12") (pintype "power_in"))
      (node (ref "J3") (pin "S1") (pinfunction "SHELL_GND_S1") (pintype "power_in"))
      (node (ref "J3") (pin "S2") (pinfunction "SHELL_GND_S2") (pintype "power_in"))
      (node (ref "J3") (pin "S3") (pinfunction "SHELL_GND_S3") (pintype "power_in"))
      (node (ref "J3") (pin "S4") (pinfunction "SHELL_GND_S4") (pintype "power_in"))
      (node (ref "K1") (pin "2") (pinfunction "2_2") (pintype "passive"))
      (node (ref "K1") (pin "4") (pinfunction "4_4") (pintype "passive"))
      (node (ref "K2") (pin "2") (pinfunction "2_2") (pintype "passive"))
      (node (ref "K2") (pin "4") (pinfunction "4_4") (pintype "passive"))
      (node (ref "P3") (pin "1") (pinfunction "1_1") (pintype "passive"))
      (node (ref "P4") (pin "1") (pinfunction "1_1") (pintype "passive"))
      (node (ref "P5") (pin "5") (pinfunction "5_5") (pintype "passive"))
      (node (ref "P6") (pin "4") (pinfunction "4_4") (pintype "passive"))
      (node (ref "P7") (pin "1") (pinfunction "1_1") (pintype "passive"))
      (node (ref "P8") (pin "1") (pinfunction "1_1") (pintype "passive"))
      (node (ref "R14") (pin "1") (pinfunction "1_1") (pintype "passive"))
      (node (ref "R2") (pin "2") (pinfunction "2_2") (pintype "passive"))
      (node (ref "R24") (pin "1") (pinfunction "1_1") (pintype "passive"))
      (node (ref "R26") (pin "2") (pinfunction "2_2") (pintype "passive"))
      (node (ref "R27") (pin "1") (pinfunction "1_1") (pintype "passive"))
      (node (ref "R3") (pin "1") (pinfunction "1_1") (pintype "passive"))
      (node (ref "R9") (pin "1") (pinfunction "1_1") (pintype "passive"))
      (node (ref "U1") (pin "10") (pinfunction "PGND3_10") (pintype "power_in"))
      (node (ref "U1") (pin "12") (pinfunction "COMPP_12") (pintype "input"))
      (node (ref "U1") (pin "13") (pinfunction "COMPN_13") (pintype "input"))
      (node (ref "U1") (pin "14") (pinfunction "GND_14") (pintype "power_in"))
      (node (ref "U1") (pin "20") (pinfunction "GND_20") (pintype "power_in"))
      (node (ref "U1") (pin "28") (pinfunction "GND_28") (pintype "power_in"))
      (node (ref "U1") (pin "29") (pinfunction "Thermal_pad_29") (pintype "power_in"))
      (node (ref "U1") (pin "6") (pinfunction "PGND1_6") (pintype "power_in"))
      (node (ref "U1") (pin "7") (pinfunction "PGND2_7") (pintype "power_in"))
      (node (ref "U2") (pin "2") (pinfunction "GND_2") (pintype "power_in"))
      (node (ref "U3") (pin "2") (pinfunction "GND_2") (pintype "passive"))
      (node (ref "U4") (pin "23") (pinfunction "VSS_1_23") (pintype "power_in"))
      (node (ref "U4") (pin "35") (pinfunction "VSS_2_35") (pintype "power_in"))
      (node (ref "U4") (pin "44") (pinfunction "BOOT0_44") (pintype "input"))
      (node (ref "U4") (pin "47") (pinfunction "VSS_3_47") (pintype "power_in"))
      (node (ref "U5") (pin "18") (pinfunction "GND_18") (pintype "passive"))
      (node (ref "U5") (pin "21") (pinfunction "GND_21") (pintype "passive"))
      (node (ref "U5") (pin "26") (pinfunction "TEST_26") (pintype "passive"))
      (node (ref "U5") (pin "7") (pinfunction "GND_7") (pintype "passive"))
      (node (ref "U6") (pin "13") (pinfunction "GND_13") (pintype "power_in"))
      (node (ref "U6") (pin "5") (pinfunction "TEST_5") (pintype "input"))
      (node (ref "U7") (pin "4") (pinfunction "GND_4") (pintype "power_in"))
      (node (ref "U7") (pin "7") (pinfunction "REF1_7") (pintype "input"))
      (node (ref "U8") (pin "4") (pinfunction "GND_4") (pintype "power_in"))
      (node (ref "U8") (pin "7") (pinfunction "REF1_7") (pintype "input"))
      (node (ref "U9") (pin "2") (pinfunction "GND_2") (pintype "passive"))
      (node (ref "Y1") (pin "2") (pinfunction "GND_2") (pintype "power_in"))
    )
    (net (code "51") (name "Net-(D1-C)") (class "Default")
      (node (ref "D1") (pin "1") (pinfunction "C_1") (pintype "passive"))
      (node (ref "R2") (pin "1") (pinfunction "1_1") (pintype "passive"))
    )
    (net (code "52") (name "Net-(D2-K)") (class "Default")
      (node (ref "C6") (pin "1") (pinfunction "1_1") (pintype "passive"))
      (node (ref "C8") (pin "1") (pinfunction "1_1") (pintype "passive"))
      (node (ref "D2") (pin "2") (pinfunction "K_2") (pintype "passive"))
      (node (ref "L1") (pin "1") (pinfunction "1_1") (pintype "passive"))
      (node (ref "U3") (pin "6") (pinfunction "SW_6") (pintype "passive"))
    )
    (net (code "53") (name "Net-(D4-K)") (class "Default")
      (node (ref "C11") (pin "2") (pinfunction "2_2") (pintype "passive"))
      (node (ref "D4") (pin "2") (pinfunction "K_2") (pintype "passive"))
      (node (ref "R5") (pin "1") (pinfunction "1_1") (pintype "passive"))
      (node (ref "U3") (pin "5") (pinfunction "IN_5") (pintype "passive"))
    )
    (net (code "54") (name "Net-(J3-CC1)") (class "Default")
      (node (ref "J3") (pin "A5") (pinfunction "CC1_A5") (pintype "bidirectional"))
      (node (ref "R26") (pin "1") (pinfunction "1_1") (pintype "passive"))
    )
    (net (code "55") (name "Net-(J3-CC2)") (class "Default")
      (node (ref "J3") (pin "B5") (pinfunction "CC2_B5") (pintype "bidirectional"))
      (node (ref "R27") (pin "2") (pinfunction "2_2") (pintype "passive"))
    )
    (net (code "56") (name "Net-(R25-Pad1)") (class "Default")
      (node (ref "R25") (pin "1") (pinfunction "1_1") (pintype "passive"))
      (node (ref "S1") (pin "2") (pinfunction "2_2") (pintype "passive"))
    )
    (net (code "57") (name "Net-(U1-CPH)") (class "Default")
      (node (ref "C7") (pin "2") (pinfunction "2_2") (pintype "passive"))
      (node (ref "U1") (pin "2") (pinfunction "CPH_2") (pintype "power_in"))
    )
    (net (code "58") (name "Net-(U1-CPL)") (class "Default")
      (node (ref "C7") (pin "1") (pinfunction "1_1") (pintype "passive"))
      (node (ref "U1") (pin "1") (pinfunction "CPL_1") (pintype "power_in"))
    )
    (net (code "59") (name "Net-(U1-VCP)") (class "Default")
      (node (ref "C3") (pin "1") (pinfunction "1_1") (pintype "passive"))
      (node (ref "U1") (pin "3") (pinfunction "VCP_3") (pintype "power_in"))
    )
    (net (code "60") (name "Net-(U2-CBYP)") (class "Default")
      (node (ref "C4") (pin "2") (pinfunction "2_2") (pintype "passive"))
      (node (ref "U2") (pin "4") (pinfunction "CBYP_4") (pintype "passive"))
    )
    (net (code "61") (name "Net-(U3-BS)") (class "Default")
      (node (ref "C6") (pin "2") (pinfunction "2_2") (pintype "passive"))
      (node (ref "C8") (pin "2") (pinfunction "2_2") (pintype "passive"))
      (node (ref "U3") (pin "1") (pinfunction "BS_1") (pintype "passive"))
    )
    (net (code "62") (name "Net-(U3-EN)") (class "Default")
      (node (ref "R5") (pin "2") (pinfunction "2_2") (pintype "passive"))
      (node (ref "U3") (pin "4") (pinfunction "EN_4") (pintype "passive"))
    )
    (net (code "63") (name "Net-(U3-FB)") (class "Default")
      (node (ref "C5") (pin "1") (pinfunction "1_1") (pintype "passive"))
      (node (ref "R1") (pin "1") (pinfunction "1_1") (pintype "passive"))
      (node (ref "R3") (pin "2") (pinfunction "2_2") (pintype "passive"))
      (node (ref "U3") (pin "3") (pinfunction "FB_3") (pintype "passive"))
    )
    (net (code "64") (name "Net-(U4A-PD0-OSC_IN)") (class "Default")
      (node (ref "U4") (pin "5") (pinfunction "PD0-OSC_IN_5") (pintype "bidirectional"))
      (node (ref "Y1") (pin "3") (pinfunction "Output_3") (pintype "output"))
    )
    (net (code "65") (name "Net-(U4A-PD1)") (class "Default")
      (node (ref "U4") (pin "6") (pinfunction "PD1_6") (pintype "bidirectional"))
      (node (ref "Y1") (pin "1") (pinfunction "Input_1") (pintype "input"))
    )
    (net (code "66") (name "Net-(U5-3V3OUT)") (class "Default")
      (node (ref "C22") (pin "1") (pinfunction "1_1") (pintype "passive"))
      (node (ref "U5") (pin "17") (pinfunction "3V3OUT_17") (pintype "passive"))
    )
    (net (code "67") (name "VBUS") (class "Default")
      (node (ref "D5") (pin "1") (pinfunction "A_1") (pintype "passive"))
      (node (ref "J3") (pin "A4") (pinfunction "VBUS_A_A4") (pintype "power_in"))
      (node (ref "J3") (pin "A9") (pinfunction "VBUS_A_A9") (pintype "power_in"))
      (node (ref "J3") (pin "B4") (pinfunction "VBUS_B_B4") (pintype "power_in"))
      (node (ref "J3") (pin "B9") (pinfunction "VBUS_B_B9") (pintype "power_in"))
    )
    (net (code "68") (name "VCC") (class "Default")
      (node (ref "C12") (pin "2") (pinfunction "2_2") (pintype "passive"))
      (node (ref "C13") (pin "2") (pinfunction "2_2") (pintype "passive"))
      (node (ref "C14") (pin "2") (pinfunction "2_2") (pintype "passive"))
      (node (ref "C15") (pin "2") (pinfunction "2_2") (pintype "passive"))
      (node (ref "C16") (pin "2") (pinfunction "2_2") (pintype "passive"))
      (node (ref "C3") (pin "2") (pinfunction "2_2") (pintype "passive"))
      (node (ref "D3") (pin "2") (pinfunction "K_2") (pintype "passive"))
      (node (ref "D4") (pin "1") (pinfunction "A_1") (pintype "passive"))
      (node (ref "DR1") (pin "1") (pinfunction "A_1") (pintype "passive"))
      (node (ref "U1") (pin "11") (pinfunction "VM_11") (pintype "power_in"))
      (node (ref "U1") (pin "4") (pinfunction "VM_4") (pintype "power_in"))
    )
    (net (code "69") (name "VCC_IN") (class "Default")
      (node (ref "D3") (pin "1") (pinfunction "A_1") (pintype "passive"))
      (node (ref "J2") (pin "1") (pinfunction "1_1") (pintype "passive"))
    )
    (net (code "70") (name "unconnected-(H1-Pad11)") (class "Default")
      (node (ref "H1") (pin "11") (pinfunction "11_11") (pintype "passive"))
    )
    (net (code "71") (name "unconnected-(H2-Pad11)") (class "Default")
      (node (ref "H2") (pin "11") (pinfunction "11_11") (pintype "passive"))
    )
    (net (code "72") (name "unconnected-(H3-Pad11)") (class "Default")
      (node (ref "H3") (pin "11") (pinfunction "11_11") (pintype "passive"))
    )
    (net (code "73") (name "unconnected-(H4-Pad11)") (class "Default")
      (node (ref "H4") (pin "11") (pinfunction "11_11") (pintype "passive"))
    )
    (net (code "74") (name "unconnected-(J3-SBU1-PadA8)") (class "Default")
      (node (ref "J3") (pin "A8") (pinfunction "SBU1_A8") (pintype "bidirectional+no_connect"))
    )
    (net (code "75") (name "unconnected-(J3-SBU2-PadB8)") (class "Default")
      (node (ref "J3") (pin "B8") (pinfunction "SBU2_B8") (pintype "bidirectional+no_connect"))
    )
    (net (code "76") (name "unconnected-(U1-NC-Pad21)") (class "Default")
      (node (ref "U1") (pin "21") (pinfunction "NC_21") (pintype "passive+no_connect"))
    )
    (net (code "77") (name "unconnected-(U1-~{COMPO}-Pad19)") (class "Default")
      (node (ref "U1") (pin "19") (pinfunction "~{COMPO}_19") (pintype "open_collector+no_connect"))
    )
    (net (code "78") (name "unconnected-(U4A-PA11-Pad32)") (class "Default")
      (node (ref "U4") (pin "32") (pinfunction "PA11_32") (pintype "bidirectional"))
    )
    (net (code "79") (name "unconnected-(U4A-PA12-Pad33)") (class "Default")
      (node (ref "U4") (pin "33") (pinfunction "PA12_33") (pintype "bidirectional"))
    )
    (net (code "80") (name "unconnected-(U4A-PB2-Pad20)") (class "Default")
      (node (ref "U4") (pin "20") (pinfunction "PB2_20") (pintype "bidirectional+no_connect"))
    )
    (net (code "81") (name "unconnected-(U5-CBUS0-Pad23)") (class "Default")
      (node (ref "U5") (pin "23") (pinfunction "CBUS0_23") (pintype "passive"))
    )
    (net (code "82") (name "unconnected-(U5-CBUS1-Pad22)") (class "Default")
      (node (ref "U5") (pin "22") (pinfunction "CBUS1_22") (pintype "passive"))
    )
    (net (code "83") (name "unconnected-(U5-CBUS2-Pad13)") (class "Default")
      (node (ref "U5") (pin "13") (pinfunction "CBUS2_13") (pintype "passive"))
    )
    (net (code "84") (name "unconnected-(U5-CBUS3-Pad14)") (class "Default")
      (node (ref "U5") (pin "14") (pinfunction "CBUS3_14") (pintype "passive"))
    )
    (net (code "85") (name "unconnected-(U5-CBUS4-Pad12)") (class "Default")
      (node (ref "U5") (pin "12") (pinfunction "CBUS4_12") (pintype "passive"))
    )
    (net (code "86") (name "unconnected-(U5-CTS-Pad11)") (class "Default")
      (node (ref "U5") (pin "11") (pinfunction "CTS_11") (pintype "passive"))
    )
    (net (code "87") (name "unconnected-(U5-DCD-Pad10)") (class "Default")
      (node (ref "U5") (pin "10") (pinfunction "DCD_10") (pintype "passive"))
    )
    (net (code "88") (name "unconnected-(U5-DSR-Pad9)") (class "Default")
      (node (ref "U5") (pin "9") (pinfunction "DSR_9") (pintype "passive"))
    )
    (net (code "89") (name "unconnected-(U5-DTR-Pad2)") (class "Default")
      (node (ref "U5") (pin "2") (pinfunction "DTR_2") (pintype "passive"))
    )
    (net (code "90") (name "unconnected-(U5-NC-Pad8)") (class "Default")
      (node (ref "U5") (pin "8") (pinfunction "NC_8") (pintype "passive"))
    )
    (net (code "91") (name "unconnected-(U5-NC-Pad24)") (class "Default")
      (node (ref "U5") (pin "24") (pinfunction "NC_24") (pintype "passive"))
    )
    (net (code "92") (name "unconnected-(U5-OSCI-Pad27)") (class "Default")
      (node (ref "U5") (pin "27") (pinfunction "OSCI_27") (pintype "passive"))
    )
    (net (code "93") (name "unconnected-(U5-OSCO-Pad28)") (class "Default")
      (node (ref "U5") (pin "28") (pinfunction "OSCO_28") (pintype "passive"))
    )
    (net (code "94") (name "unconnected-(U5-RESET-Pad19)") (class "Default")
      (node (ref "U5") (pin "19") (pinfunction "RESET_19") (pintype "passive"))
    )
    (net (code "95") (name "unconnected-(U5-RI-Pad6)") (class "Default")
      (node (ref "U5") (pin "6") (pinfunction "RI_6") (pintype "passive"))
    )
    (net (code "96") (name "unconnected-(U5-RTS-Pad3)") (class "Default")
      (node (ref "U5") (pin "3") (pinfunction "RTS_3") (pintype "passive"))
    )
    (net (code "97") (name "unconnected-(U6-PWM-Pad14)") (class "Default")
      (node (ref "U6") (pin "14") (pinfunction "PWM_14") (pintype "output+no_connect"))
    )
    (net (code "98") (name "unconnected-(U6-TEST-Pad6)") (class "Default")
      (node (ref "U6") (pin "6") (pinfunction "TEST_6") (pintype "input+no_connect"))
    )
    (net (code "99") (name "unconnected-(U6-TEST-Pad7)") (class "Default")
      (node (ref "U6") (pin "7") (pinfunction "TEST_7") (pintype "input+no_connect"))
    )
    (net (code "100") (name "unconnected-(U6-TEST-Pad8)") (class "Default")
      (node (ref "U6") (pin "8") (pinfunction "TEST_8") (pintype "input+no_connect"))
    )
    (net (code "101") (name "unconnected-(U6-TEST-Pad9)") (class "Default")
      (node (ref "U6") (pin "9") (pinfunction "TEST_9") (pintype "input+no_connect"))
    )
    (net (code "102") (name "unconnected-(U6-TEST-Pad10)") (class "Default")
      (node (ref "U6") (pin "10") (pinfunction "TEST_10") (pintype "input+no_connect"))
    )
    (net (code "103") (name "unconnected-(U9-NC-Pad5)") (class "Default")
      (node (ref "U9") (pin "5") (pinfunction "NC_5") (pintype "passive+no_connect"))
    )
    (net (code "104") (name "unconnected-(U9-NC-Pad8)") (class "Default")
      (node (ref "U9") (pin "8") (pinfunction "NC_8") (pintype "passive+no_connect"))
    )
  )
)
